# motordriver.net
KiCad netlist of a schematic drawn in Altium Designer
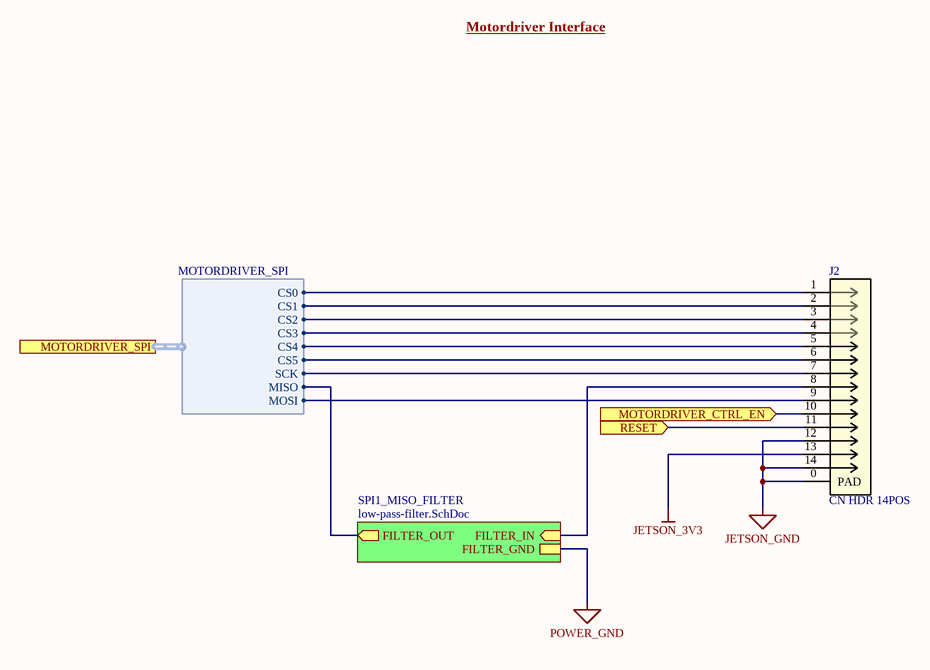
[diagram p0: motordriver.SchDoc]

(export (version "E")
  (design (tool "Eeschema 10.0.6"))
  (components
    (comp (ref "J2")
      (value "CN HDR 14POS")
      (footprint "CN HDR 14POS SMD 1.5MM")
      (description "Connector Header 14 Position")
      (libsource (lib "Connector_Library") (part "CN HDR 14POS"))
    )
  )
  (nets
    (net (code "2") (name "/CS0") (class "Default")
      (node (ref "J2") (pin "1") (pinfunction "1_1") (pintype "passive"))
    )
    (net (code "3") (name "/CS1") (class "Default")
      (node (ref "J2") (pin "2") (pinfunction "2_2") (pintype "passive"))
    )
    (net (code "4") (name "/CS2") (class "Default")
      (node (ref "J2") (pin "3") (pinfunction "3_3") (pintype "passive"))
    )
    (net (code "5") (name "/CS3") (class "Default")
      (node (ref "J2") (pin "4") (pinfunction "4_4") (pintype "passive"))
    )
    (net (code "6") (name "/CS4") (class "Default")
      (node (ref "J2") (pin "5") (pinfunction "5_5") (pintype "passive"))
    )
    (net (code "7") (name "/CS5") (class "Default")
      (node (ref "J2") (pin "6") (pinfunction "6_6") (pintype "passive"))
    )
    (net (code "8") (name "/FILTER_IN") (class "Default")
      (node (ref "J2") (pin "8") (pinfunction "8_8") (pintype "passive"))
    )
    (net (code "10") (name "/MOSI") (class "Default")
      (node (ref "J2") (pin "9") (pinfunction "9_9") (pintype "passive"))
    )
    (net (code "11") (name "/MOTORDRIVER_CTRL_EN") (class "Default")
      (node (ref "J2") (pin "10") (pinfunction "10_10") (pintype "passive"))
    )
    (net (code "12") (name "/RESET") (class "Default")
      (node (ref "J2") (pin "11") (pinfunction "11_11") (pintype "passive"))
    )
    (net (code "13") (name "/SCK") (class "Default")
      (node (ref "J2") (pin "7") (pinfunction "7_7") (pintype "passive"))
    )
    (net (code "15") (name "JETSON_3V3") (class "Default")
      (node (ref "J2") (pin "13") (pinfunction "13_13") (pintype "passive"))
    )
    (net (code "16") (name "JETSON_GND") (class "Default")
      (node (ref "J2") (pin "0") (pinfunction "PAD_0") (pintype "passive"))
      (node (ref "J2") (pin "12") (pinfunction "12_12") (pintype "passive"))
      (node (ref "J2") (pin "14") (pinfunction "14_14") (pintype "passive"))
    )
  )
)
